# tanklight.net
KiCad netlist of a schematic drawn in EAGLE
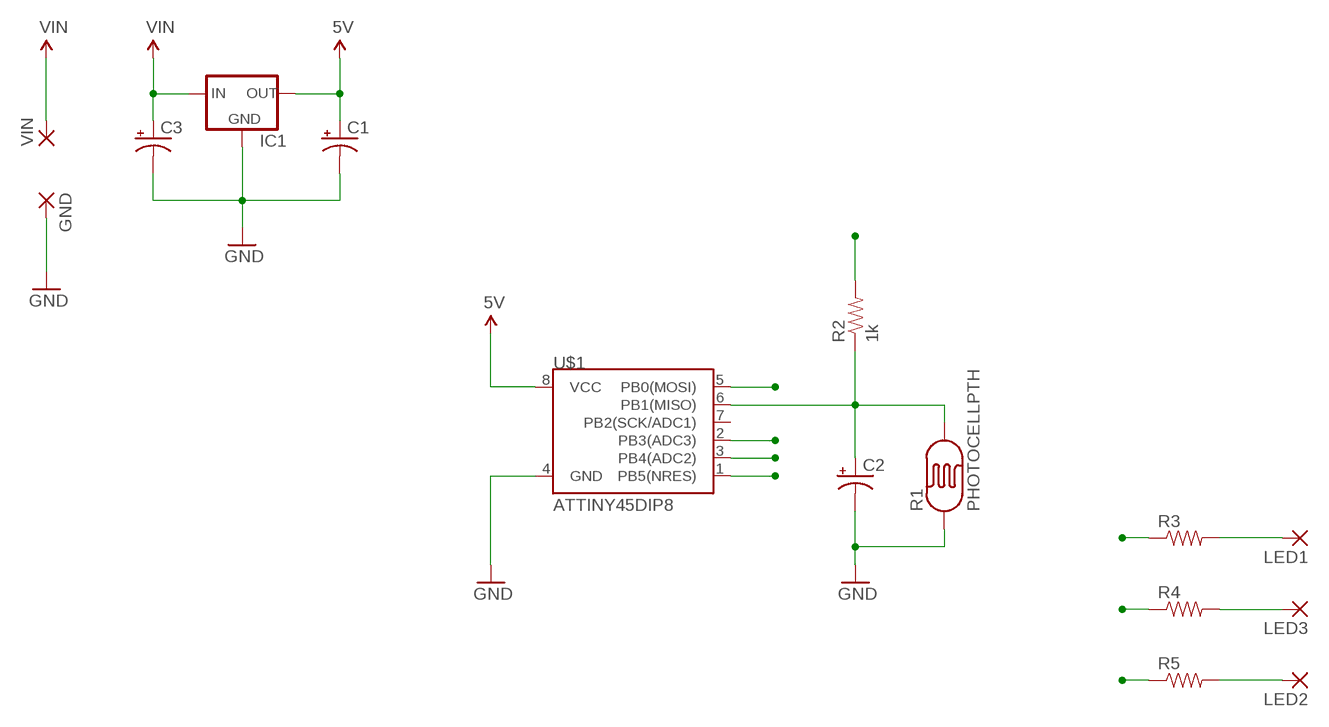
[diagram p0: schematic, sheet 1]

(export (version "E")
  (design (tool "Eeschema 10.0.6"))
  (components
    (comp (ref "C1")
      (value "CAP_POLPTH2")
      (footprint "eagle-import:CPOL-RADIAL-10UF-25V")
      (libsource (lib "eagle-import") (part "CAP_POLPTH2"))
    )
    (comp (ref "C2")
      (value "CAP_POLPTH1")
      (footprint "eagle-import:CPOL-RADIAL-100UF-25V")
      (libsource (lib "eagle-import") (part "CAP_POLPTH1"))
    )
    (comp (ref "C3")
      (value "CAP_POLPTH2")
      (footprint "eagle-import:CPOL-RADIAL-10UF-25V")
      (libsource (lib "eagle-import") (part "CAP_POLPTH2"))
    )
    (comp (ref "GND")
      (value "2,54/1,0")
      (footprint "eagle-import:2,54_1,0")
      (libsource (lib "eagle-import") (part "2,54/1,0"))
    )
    (comp (ref "IC1")
      (value "V_REG_78XXSINK")
      (footprint "eagle-import:TO220-IGO")
      (libsource (lib "eagle-import") (part "V_REG_78XXSINK"))
    )
    (comp (ref "LED1")
      (value "2,54/1,0")
      (footprint "eagle-import:2,54_1,0")
      (libsource (lib "eagle-import") (part "2,54/1,0"))
    )
    (comp (ref "LED2")
      (value "2,54/1,0")
      (footprint "eagle-import:2,54_1,0")
      (libsource (lib "eagle-import") (part "2,54/1,0"))
    )
    (comp (ref "LED3")
      (value "2,54/1,0")
      (footprint "eagle-import:2,54_1,0")
      (libsource (lib "eagle-import") (part "2,54/1,0"))
    )
    (comp (ref "R1")
      (value "PHOTOCELLPTH")
      (footprint "eagle-import:PHOTOCELL")
      (libsource (lib "eagle-import") (part "PHOTOCELLPTH"))
    )
    (comp (ref "R2")
      (value "1k")
      (footprint "eagle-import:AXIAL-0.4")
      (libsource (lib "eagle-import") (part "RESISTORPTH-1/4W"))
    )
    (comp (ref "R3")
      (value "RESISTORPTH-1/4W")
      (footprint "eagle-import:AXIAL-0.4")
      (libsource (lib "eagle-import") (part "RESISTORPTH-1/4W"))
    )
    (comp (ref "R4")
      (value "RESISTORPTH-1/4W")
      (footprint "eagle-import:AXIAL-0.4")
      (libsource (lib "eagle-import") (part "RESISTORPTH-1/4W"))
    )
    (comp (ref "R5")
      (value "RESISTORPTH-1/4W")
      (footprint "eagle-import:AXIAL-0.4")
      (libsource (lib "eagle-import") (part "RESISTORPTH-1/4W"))
    )
    (comp (ref "U$1")
      (value "ATTINY45DIP8")
      (footprint "eagle-import:DIP08")
      (libsource (lib "eagle-import") (part "ATTINY45DIP8"))
    )
    (comp (ref "VIN")
      (value "2,54/1,0")
      (footprint "eagle-import:2,54_1,0")
      (libsource (lib "eagle-import") (part "2,54/1,0"))
    )
  )
  (nets
    (net (code "1") (name "/LED1") (class "Default")
      (node (ref "R3") (pin "P$1") (pinfunction "1_P$1") (pintype "passive"))
      (node (ref "U$1") (pin "5") (pinfunction "PB0(MOSI)_5") (pintype "bidirectional"))
    )
    (net (code "2") (name "/LED2") (class "Default")
      (node (ref "R5") (pin "P$1") (pinfunction "1_P$1") (pintype "passive"))
      (node (ref "U$1") (pin "3") (pinfunction "PB4(ADC2)_3") (pintype "bidirectional"))
    )
    (net (code "3") (name "/LED3") (class "Default")
      (node (ref "R4") (pin "P$1") (pinfunction "1_P$1") (pintype "passive"))
      (node (ref "U$1") (pin "2") (pinfunction "PB3(ADC3)_2") (pintype "bidirectional"))
    )
    (net (code "4") (name "5V") (class "Default")
      (node (ref "C1") (pin "1") (pinfunction "+_1") (pintype "passive"))
      (node (ref "IC1") (pin "OUT") (pinfunction "OUT_OUT") (pintype "output"))
      (node (ref "R2") (pin "P$2") (pinfunction "2_P$2") (pintype "passive"))
      (node (ref "U$1") (pin "1") (pinfunction "PB5(NRES)_1") (pintype "bidirectional"))
      (node (ref "U$1") (pin "8") (pinfunction "VCC_8") (pintype "bidirectional"))
    )
    (net (code "5") (name "GND") (class "Default")
      (node (ref "C1") (pin "2") (pinfunction "-_2") (pintype "passive"))
      (node (ref "C2") (pin "2") (pinfunction "-_2") (pintype "passive"))
      (node (ref "C3") (pin "2") (pinfunction "-_2") (pintype "passive"))
      (node (ref "GND") (pin "1") (pinfunction "P_1") (pintype "passive"))
      (node (ref "IC1") (pin "GND") (pinfunction "GND_GND") (pintype "input"))
      (node (ref "R1") (pin "1") (pinfunction "P$1_1") (pintype "bidirectional"))
      (node (ref "U$1") (pin "4") (pinfunction "GND_4") (pintype "bidirectional"))
    )
    (net (code "6") (name "Net-(C2-+)") (class "Default")
      (node (ref "C2") (pin "1") (pinfunction "+_1") (pintype "passive"))
      (node (ref "R1") (pin "2") (pinfunction "P$2_2") (pintype "bidirectional"))
      (node (ref "R2") (pin "P$1") (pinfunction "1_P$1") (pintype "passive"))
      (node (ref "U$1") (pin "6") (pinfunction "PB1(MISO)_6") (pintype "bidirectional"))
    )
    (net (code "7") (name "Net-(LED1-P)") (class "Default")
      (node (ref "LED1") (pin "1") (pinfunction "P_1") (pintype "passive"))
      (node (ref "R3") (pin "P$2") (pinfunction "2_P$2") (pintype "passive"))
    )
    (net (code "8") (name "Net-(LED2-P)") (class "Default")
      (node (ref "LED2") (pin "1") (pinfunction "P_1") (pintype "passive"))
      (node (ref "R5") (pin "P$2") (pinfunction "2_P$2") (pintype "passive"))
    )
    (net (code "9") (name "Net-(LED3-P)") (class "Default")
      (node (ref "LED3") (pin "1") (pinfunction "P_1") (pintype "passive"))
      (node (ref "R4") (pin "P$2") (pinfunction "2_P$2") (pintype "passive"))
    )
    (net (code "10") (name "VIN") (class "Default")
      (node (ref "C3") (pin "1") (pinfunction "+_1") (pintype "passive"))
      (node (ref "IC1") (pin "IN") (pinfunction "IN_IN") (pintype "input"))
      (node (ref "VIN") (pin "1") (pinfunction "P_1") (pintype "passive"))
    )
    (net (code "11") (name "unconnected-(U$1-PB2(SCK{slash}ADC1)-Pad7)") (class "Default")
      (node (ref "U$1") (pin "7") (pinfunction "PB2(SCK/ADC1)_7") (pintype "bidirectional"))
    )
  )
)
